# FPGA_Multiplexer.net
KiCad netlist of a schematic drawn in Altium Designer
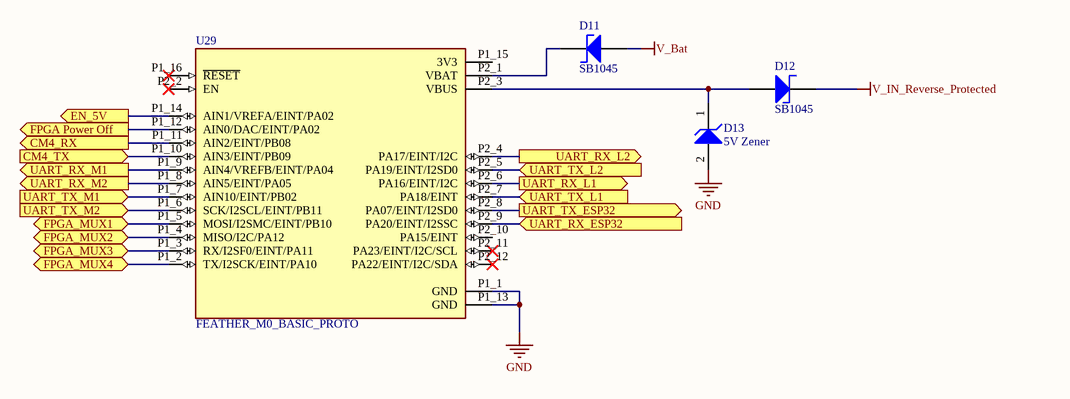
[diagram p0: FPGA_Multiplexer.SchDoc]

(export (version "E")
  (design (tool "Eeschema 10.0.6"))
  (components
    (comp (ref "D11")
      (value "SB1045")
      (footprint "FP-95570-MFG")
      (description "10.0A SCHOTTKY BARRIER RECTIFIER")
      (libsource (lib "澄 library") (part "SB1045"))
    )
    (comp (ref "D12")
      (value "SB1045")
      (footprint "FP-95570-MFG")
      (description "10.0A SCHOTTKY BARRIER RECTIFIER")
      (libsource (lib "澄 library") (part "SB1045"))
    )
    (comp (ref "D13")
      (value "5V Zener")
      (footprint "ONSC-SMA-FL-2-403AA-01_V")
      (fields (field (name "PARTNUMBER") "NS6A12AFT3G") (field (name "MANUFACTURER") "On Semiconductor"))
      (libsource (lib "Altium Content Vault") (part "ONSC-K1A2-2"))
    )
    (comp (ref "U29")
      (value "FEATHER_M0_BASIC_PROTO")
      (footprint "MODULE_FEATHER_M0_BASIC_PROTO")
      (description "ATSAMD21G18 Feather M0 Basic Proto SAM D ARMÂ® CortexÂ®-M0+ MCU 32-Bit Embedded Evaluation Board")
      (fields (field (name "MF") "Adafruit Industries") (field (name "MP") "Feather M0 Basic Proto"))
      (libsource (lib "FEATHER_M0_BASIC_PROTO") (part "FEATHER_M0_BASIC_PROTO"))
    )
  )
  (nets
    (net (code "1") (name "/CM4_RX") (class "Default")
      (node (ref "U29") (pin "P1_11") (pinfunction "AIN2/EINT/PB08_P1_11") (pintype "bidirectional"))
    )
    (net (code "2") (name "/CM4_TX") (class "Default")
      (node (ref "U29") (pin "P1_10") (pinfunction "AIN3/EINT/PB09_P1_10") (pintype "bidirectional"))
    )
    (net (code "3") (name "/EN_5V") (class "Default")
      (node (ref "U29") (pin "P1_14") (pinfunction "AIN1/VREFA/EINT/PA02_P1_14") (pintype "bidirectional"))
    )
    (net (code "4") (name "/FPGA Power Off") (class "Default")
      (node (ref "U29") (pin "P1_12") (pinfunction "AIN0/DAC/EINT/PA02_P1_12") (pintype "bidirectional"))
    )
    (net (code "5") (name "/FPGA_MUX1") (class "Default")
      (node (ref "U29") (pin "P1_5") (pinfunction "MOSI/I2SMC/EINT/PB10_P1_5") (pintype "bidirectional"))
    )
    (net (code "6") (name "/FPGA_MUX2") (class "Default")
      (node (ref "U29") (pin "P1_4") (pinfunction "MISO/I2C/PA12_P1_4") (pintype "bidirectional"))
    )
    (net (code "7") (name "/FPGA_MUX3") (class "Default")
      (node (ref "U29") (pin "P1_3") (pinfunction "RX/I2SF0/EINT/PA11_P1_3") (pintype "bidirectional"))
    )
    (net (code "8") (name "/FPGA_MUX4") (class "Default")
      (node (ref "U29") (pin "P1_2") (pinfunction "TX/I2SCK/EINT/PA10_P1_2") (pintype "bidirectional"))
    )
    (net (code "9") (name "/UART_RX_ESP32") (class "Default")
      (node (ref "U29") (pin "P2_9") (pinfunction "PA20/EINT/I2SSC_P2_9") (pintype "bidirectional"))
    )
    (net (code "10") (name "/UART_RX_L1") (class "Default")
      (node (ref "U29") (pin "P2_6") (pinfunction "PA16/EINT/I2C_P2_6") (pintype "bidirectional"))
    )
    (net (code "11") (name "/UART_RX_L2") (class "Default")
      (node (ref "U29") (pin "P2_4") (pinfunction "PA17/EINT/I2C_P2_4") (pintype "bidirectional"))
    )
    (net (code "12") (name "/UART_RX_M1") (class "Default")
      (node (ref "U29") (pin "P1_9") (pinfunction "AIN4/VREFB/EINT/PA04_P1_9") (pintype "bidirectional"))
    )
    (net (code "13") (name "/UART_RX_M2") (class "Default")
      (node (ref "U29") (pin "P1_8") (pinfunction "AIN5/EINT/PA05_P1_8") (pintype "bidirectional"))
    )
    (net (code "14") (name "/UART_TX_ESP32") (class "Default")
      (node (ref "U29") (pin "P2_8") (pinfunction "PA07/EINT/I2SD0_P2_8") (pintype "bidirectional"))
    )
    (net (code "15") (name "/UART_TX_L1") (class "Default")
      (node (ref "U29") (pin "P2_7") (pinfunction "PA18/EINT_P2_7") (pintype "bidirectional"))
    )
    (net (code "16") (name "/UART_TX_L2") (class "Default")
      (node (ref "U29") (pin "P2_5") (pinfunction "PA19/EINT/I2SD0_P2_5") (pintype "bidirectional"))
    )
    (net (code "17") (name "/UART_TX_M1") (class "Default")
      (node (ref "U29") (pin "P1_7") (pinfunction "AIN10/EINT/PB02_P1_7") (pintype "bidirectional"))
    )
    (net (code "18") (name "/UART_TX_M2") (class "Default")
      (node (ref "U29") (pin "P1_6") (pinfunction "SCK/I2SCL/EINT/PB11_P1_6") (pintype "bidirectional"))
    )
    (net (code "19") (name "GND") (class "Default")
      (node (ref "D13") (pin "2") (pinfunction "A_2") (pintype "passive"))
      (node (ref "U29") (pin "P1_1") (pinfunction "GND_P1_1") (pintype "power_in"))
      (node (ref "U29") (pin "P1_13") (pinfunction "GND_P1_13") (pintype "power_in"))
    )
    (net (code "20") (name "Net-(D11-K)") (class "Default")
      (node (ref "D11") (pin "2") (pinfunction "K_2") (pintype "passive"))
      (node (ref "U29") (pin "P2_1") (pinfunction "VBAT_P2_1") (pintype "power_in"))
    )
    (net (code "21") (name "Net-(D12-A)") (class "Default")
      (node (ref "D12") (pin "1") (pinfunction "A_1") (pintype "passive"))
      (node (ref "D13") (pin "1") (pinfunction "K_1") (pintype "passive"))
      (node (ref "U29") (pin "P2_3") (pinfunction "VBUS_P2_3") (pintype "power_in"))
    )
    (net (code "22") (name "V_Bat") (class "Default")
      (node (ref "D11") (pin "1") (pinfunction "A_1") (pintype "passive"))
    )
    (net (code "23") (name "V_IN_Reverse_Protected") (class "Default")
      (node (ref "D12") (pin "2") (pinfunction "K_2") (pintype "passive"))
    )
    (net (code "24") (name "unconnected-(U29-3V3-PadP1_15)") (class "Default")
      (node (ref "U29") (pin "P1_15") (pinfunction "3V3_P1_15") (pintype "power_in"))
    )
    (net (code "25") (name "unconnected-(U29-EN-PadP2_2)") (class "Default")
      (node (ref "U29") (pin "P2_2") (pinfunction "EN_P2_2") (pintype "input+no_connect"))
    )
    (net (code "26") (name "unconnected-(U29-PA15{slash}EINT-PadP2_10)") (class "Default")
      (node (ref "U29") (pin "P2_10") (pinfunction "PA15/EINT_P2_10") (pintype "bidirectional"))
    )
    (net (code "27") (name "unconnected-(U29-PA22{slash}EINT{slash}I2C{slash}SDA-PadP2_12)") (class "Default")
      (node (ref "U29") (pin "P2_12") (pinfunction "PA22/EINT/I2C/SDA_P2_12") (pintype "bidirectional+no_connect"))
    )
    (net (code "28") (name "unconnected-(U29-PA23{slash}EINT{slash}I2C{slash}SCL-PadP2_11)") (class "Default")
      (node (ref "U29") (pin "P2_11") (pinfunction "PA23/EINT/I2C/SCL_P2_11") (pintype "bidirectional+no_connect"))
    )
    (net (code "29") (name "unconnected-(U29-~{RESET}-PadP1_16)") (class "Default")
      (node (ref "U29") (pin "P1_16") (pinfunction "~{RESET}_P1_16") (pintype "input+no_connect"))
    )
  )
)
